# Measurements.net
KiCad netlist of a schematic drawn in Altium Designer
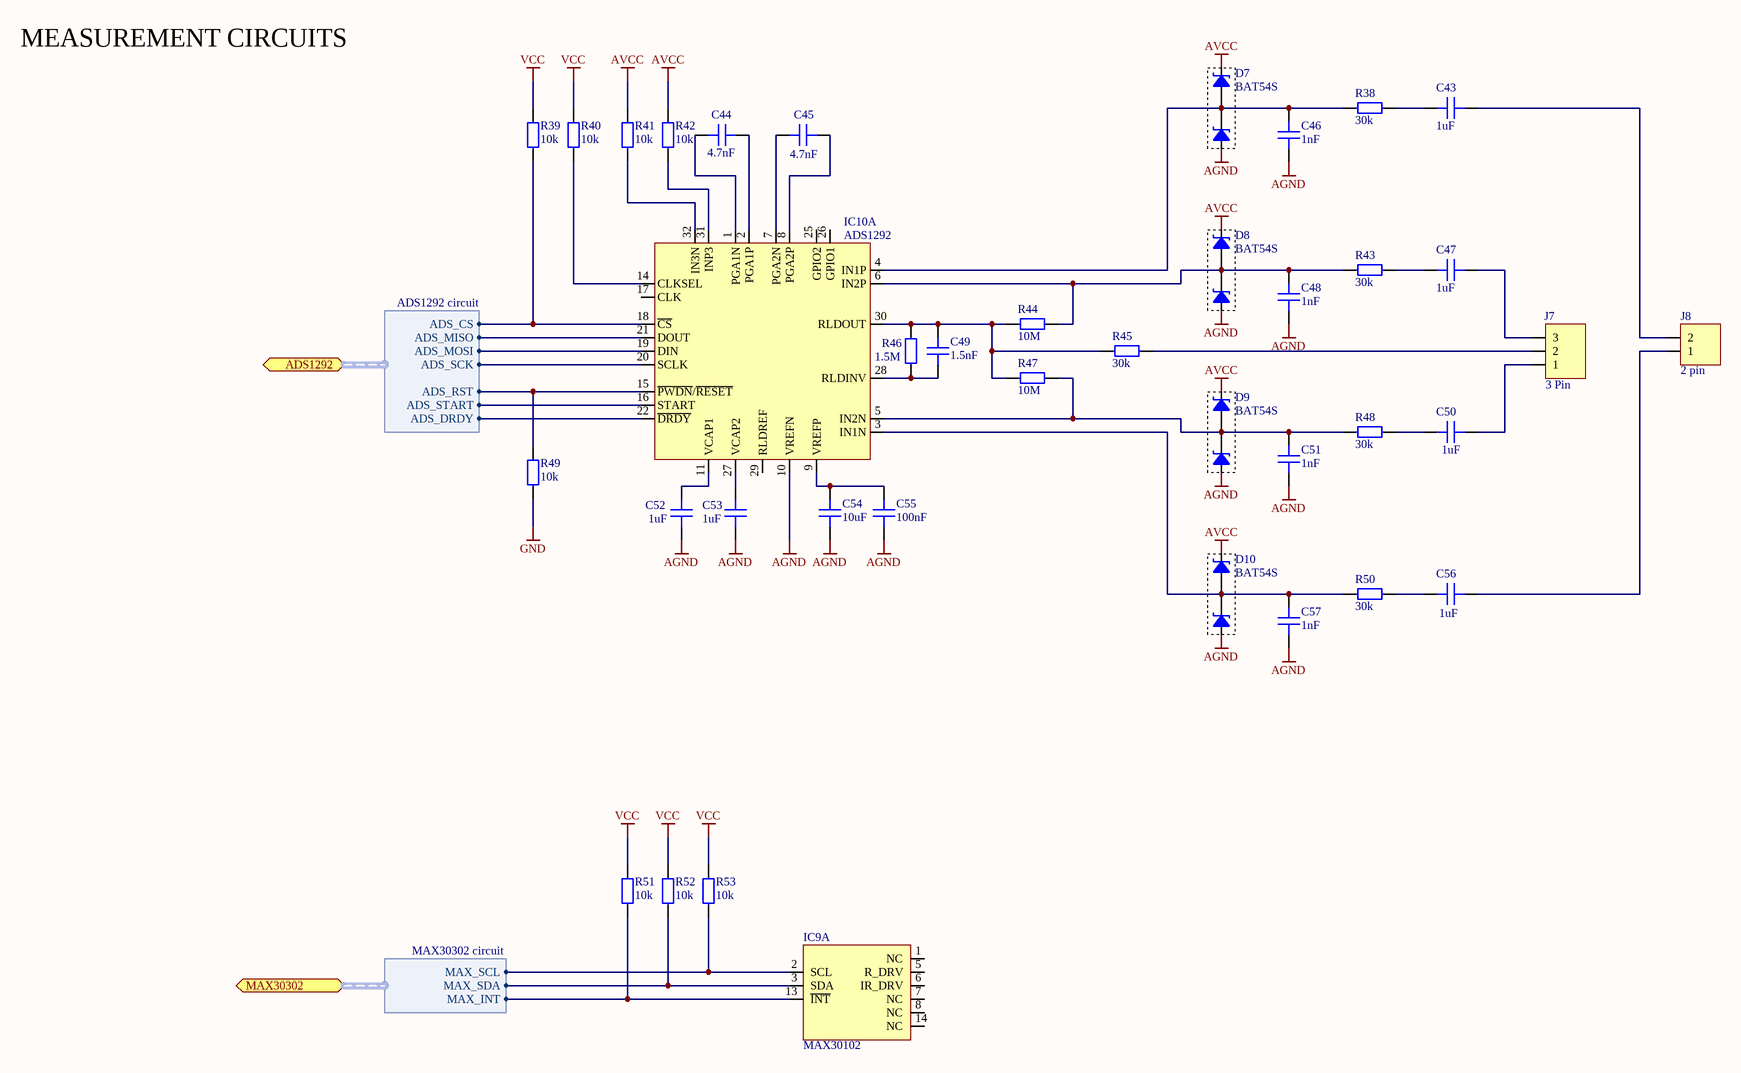
[diagram p0: Measurements.SchDoc]

(export (version "E")
  (design (tool "Eeschema 10.0.6"))
  (components
    (comp (ref "C43")
      (value "1uF")
      (footprint "CAP 0603")
      (description "SMT Capacitor")
      (libsource (lib "Passive") (part "Capacitor"))
    )
    (comp (ref "C44")
      (value "4.7nF")
      (footprint "CAP 0603")
      (description "SMT Capacitor")
      (libsource (lib "Passive") (part "Capacitor"))
    )
    (comp (ref "C45")
      (value "4.7nF")
      (footprint "CAP 0603")
      (description "SMT Capacitor")
      (libsource (lib "Passive") (part "Capacitor"))
    )
    (comp (ref "C46")
      (value "1nF")
      (footprint "CAP 0603")
      (description "SMT Capacitor")
      (libsource (lib "Passive") (part "Capacitor"))
    )
    (comp (ref "C47")
      (value "1uF")
      (footprint "CAP 0603")
      (description "SMT Capacitor")
      (libsource (lib "Passive") (part "Capacitor"))
    )
    (comp (ref "C48")
      (value "1nF")
      (footprint "CAP 0603")
      (description "SMT Capacitor")
      (libsource (lib "Passive") (part "Capacitor"))
    )
    (comp (ref "C49")
      (value "1.5nF")
      (footprint "CAP 0603")
      (description "SMT Capacitor")
      (libsource (lib "Passive") (part "Capacitor"))
    )
    (comp (ref "C50")
      (value "1uF")
      (footprint "CAP 0603")
      (description "SMT Capacitor")
      (libsource (lib "Passive") (part "Capacitor"))
    )
    (comp (ref "C51")
      (value "1nF")
      (footprint "CAP 0603")
      (description "SMT Capacitor")
      (libsource (lib "Passive") (part "Capacitor"))
    )
    (comp (ref "C52")
      (value "1uF")
      (footprint "CAP 0603")
      (description "SMT Capacitor")
      (libsource (lib "Passive") (part "Capacitor"))
    )
    (comp (ref "C53")
      (value "1uF")
      (footprint "CAP 0603")
      (description "SMT Capacitor")
      (libsource (lib "Passive") (part "Capacitor"))
    )
    (comp (ref "C54")
      (value "10uF")
      (footprint "CAP 0603")
      (description "SMT Capacitor")
      (libsource (lib "Passive") (part "Capacitor"))
    )
    (comp (ref "C55")
      (value "100nF")
      (footprint "CAP 0603")
      (description "SMT Capacitor")
      (libsource (lib "Passive") (part "Capacitor"))
    )
    (comp (ref "C56")
      (value "1uF")
      (footprint "CAP 0603")
      (description "SMT Capacitor")
      (libsource (lib "Passive") (part "Capacitor"))
    )
    (comp (ref "C57")
      (value "1nF")
      (footprint "CAP 0603")
      (description "SMT Capacitor")
      (libsource (lib "Passive") (part "Capacitor"))
    )
    (comp (ref "D7")
      (value "BAT54S")
      (footprint "SOT23")
      (description "Schottky barrier diodes")
      (libsource (lib "Diodes") (part "BAT54S"))
    )
    (comp (ref "D8")
      (value "BAT54S")
      (footprint "SOT23")
      (description "Schottky barrier diodes")
      (libsource (lib "Diodes") (part "BAT54S"))
    )
    (comp (ref "D9")
      (value "BAT54S")
      (footprint "SOT23")
      (description "Schottky barrier diodes")
      (libsource (lib "Diodes") (part "BAT54S"))
    )
    (comp (ref "D10")
      (value "BAT54S")
      (footprint "SOT23")
      (description "Schottky barrier diodes")
      (libsource (lib "Diodes") (part "BAT54S"))
    )
    (comp (ref "IC9")
      (value "MAX30102")
      (footprint "MAX30102")
      (description "Pulse Oximeter and Heart-Rate Sensor")
      (libsource (lib "IC") (part "MAX30102"))
    )
    (comp (ref "IC10")
      (value "ADS1292")
      (footprint "QFN 40 no via in pad")
      (description "ADS1292IRSMT Analog Front End - AFE Cmplt Lw Pwr Intgrtd AFE for ECG apps")
      (libsource (lib "IC") (part "ADS1292IRSMT"))
    )
    (comp (ref "J7")
      (value "3 Pin")
      (footprint "HDR 1x3 2.54")
      (description "3 pin header, male")
      (libsource (lib "Connectors") (part "3 Pin"))
    )
    (comp (ref "J8")
      (value "2 pin")
      (footprint "HDR 1x2 2.54")
      (description "2 pin header, male")
      (libsource (lib "Connectors") (part "2 pin"))
    )
    (comp (ref "R38")
      (value "30k")
      (footprint "RES 0603")
      (description "SMDResistor")
      (libsource (lib "Passive") (part "Resistor"))
    )
    (comp (ref "R39")
      (value "10k")
      (footprint "RES 0603")
      (description "SMDResistor")
      (libsource (lib "Passive") (part "Resistor"))
    )
    (comp (ref "R40")
      (value "10k")
      (footprint "RES 0603")
      (description "SMDResistor")
      (libsource (lib "Passive") (part "Resistor"))
    )
    (comp (ref "R41")
      (value "10k")
      (footprint "RES 0603")
      (description "SMDResistor")
      (libsource (lib "Passive") (part "Resistor"))
    )
    (comp (ref "R42")
      (value "10k")
      (footprint "RES 0603")
      (description "SMDResistor")
      (libsource (lib "Passive") (part "Resistor"))
    )
    (comp (ref "R43")
      (value "30k")
      (footprint "RES 0603")
      (description "SMDResistor")
      (libsource (lib "Passive") (part "Resistor"))
    )
    (comp (ref "R44")
      (value "10M")
      (footprint "RES 0603")
      (description "SMDResistor")
      (libsource (lib "Passive") (part "Resistor"))
    )
    (comp (ref "R45")
      (value "30k")
      (footprint "RES 0603")
      (description "SMDResistor")
      (libsource (lib "Passive") (part "Resistor"))
    )
    (comp (ref "R46")
      (value "1.5M")
      (footprint "RES 0603")
      (description "SMDResistor")
      (libsource (lib "Passive") (part "Resistor"))
    )
    (comp (ref "R47")
      (value "10M")
      (footprint "RES 0603")
      (description "SMDResistor")
      (libsource (lib "Passive") (part "Resistor"))
    )
    (comp (ref "R48")
      (value "30k")
      (footprint "RES 0603")
      (description "SMDResistor")
      (libsource (lib "Passive") (part "Resistor"))
    )
    (comp (ref "R49")
      (value "10k")
      (footprint "RES 0603")
      (description "SMDResistor")
      (libsource (lib "Passive") (part "Resistor"))
    )
    (comp (ref "R50")
      (value "30k")
      (footprint "RES 0603")
      (description "SMDResistor")
      (libsource (lib "Passive") (part "Resistor"))
    )
    (comp (ref "R51")
      (value "10k")
      (footprint "RES 0603")
      (description "SMDResistor")
      (libsource (lib "Passive") (part "Resistor"))
    )
    (comp (ref "R52")
      (value "10k")
      (footprint "RES 0603")
      (description "SMDResistor")
      (libsource (lib "Passive") (part "Resistor"))
    )
    (comp (ref "R53")
      (value "10k")
      (footprint "RES 0603")
      (description "SMDResistor")
      (libsource (lib "Passive") (part "Resistor"))
    )
  )
  (nets
    (net (code "4") (name "/ADS_CS") (class "Default")
      (node (ref "IC10") (pin "18") (pinfunction "~{CS}_18") (pintype "passive"))
      (node (ref "R39") (pin "1") (pinfunction "1_1") (pintype "passive"))
    )
    (net (code "5") (name "/ADS_DRDY") (class "Default")
      (node (ref "IC10") (pin "22") (pinfunction "~{DRDY}_22") (pintype "passive"))
    )
    (net (code "6") (name "/ADS_MISO") (class "Default")
      (node (ref "IC10") (pin "21") (pinfunction "DOUT_21") (pintype "passive"))
    )
    (net (code "7") (name "/ADS_MOSI") (class "Default")
      (node (ref "IC10") (pin "19") (pinfunction "DIN_19") (pintype "passive"))
    )
    (net (code "8") (name "/ADS_RST") (class "Default")
      (node (ref "IC10") (pin "15") (pinfunction "~{PWDN}/~{RESET}_15") (pintype "passive"))
      (node (ref "R49") (pin "2") (pinfunction "2_2") (pintype "passive"))
    )
    (net (code "9") (name "/ADS_SCK") (class "Default")
      (node (ref "IC10") (pin "20") (pinfunction "SCLK_20") (pintype "passive"))
    )
    (net (code "10") (name "/ADS_START") (class "Default")
      (node (ref "IC10") (pin "16") (pinfunction "START_16") (pintype "passive"))
    )
    (net (code "11") (name "/MAX_INT") (class "Default")
      (node (ref "IC9") (pin "13") (pinfunction "~{INT}_13") (pintype "passive"))
      (node (ref "R51") (pin "1") (pinfunction "1_1") (pintype "passive"))
    )
    (net (code "12") (name "/MAX_SCL") (class "Default")
      (node (ref "IC9") (pin "2") (pinfunction "SCL_2") (pintype "passive"))
      (node (ref "R53") (pin "1") (pinfunction "1_1") (pintype "passive"))
    )
    (net (code "13") (name "/MAX_SDA") (class "Default")
      (node (ref "IC9") (pin "3") (pinfunction "SDA_3") (pintype "passive"))
      (node (ref "R52") (pin "1") (pinfunction "1_1") (pintype "passive"))
    )
    (net (code "16") (name "AGND") (class "Default")
      (node (ref "C46") (pin "1") (pinfunction "1_1") (pintype "passive"))
      (node (ref "C48") (pin "1") (pinfunction "1_1") (pintype "passive"))
      (node (ref "C51") (pin "1") (pinfunction "1_1") (pintype "passive"))
      (node (ref "C52") (pin "1") (pinfunction "1_1") (pintype "passive"))
      (node (ref "C53") (pin "1") (pinfunction "1_1") (pintype "passive"))
      (node (ref "C54") (pin "1") (pinfunction "1_1") (pintype "passive"))
      (node (ref "C55") (pin "1") (pinfunction "1_1") (pintype "passive"))
      (node (ref "C57") (pin "1") (pinfunction "1_1") (pintype "passive"))
      (node (ref "D10") (pin "1") (pinfunction "1_1") (pintype "passive"))
      (node (ref "D7") (pin "1") (pinfunction "1_1") (pintype "passive"))
      (node (ref "D8") (pin "1") (pinfunction "1_1") (pintype "passive"))
      (node (ref "D9") (pin "1") (pinfunction "1_1") (pintype "passive"))
      (node (ref "IC10") (pin "10") (pinfunction "VREFN_10") (pintype "passive"))
    )
    (net (code "17") (name "AVCC") (class "Default")
      (node (ref "D10") (pin "2") (pinfunction "2_2") (pintype "passive"))
      (node (ref "D7") (pin "2") (pinfunction "2_2") (pintype "passive"))
      (node (ref "D8") (pin "2") (pinfunction "2_2") (pintype "passive"))
      (node (ref "D9") (pin "2") (pinfunction "2_2") (pintype "passive"))
      (node (ref "R41") (pin "2") (pinfunction "2_2") (pintype "passive"))
      (node (ref "R42") (pin "2") (pinfunction "2_2") (pintype "passive"))
    )
    (net (code "18") (name "GND") (class "Default")
      (node (ref "R49") (pin "1") (pinfunction "1_1") (pintype "passive"))
    )
    (net (code "19") (name "Net-(C43-Pad1)") (class "Default")
      (node (ref "C43") (pin "1") (pinfunction "1_1") (pintype "passive"))
      (node (ref "J8") (pin "2") (pinfunction "2_2") (pintype "passive"))
    )
    (net (code "20") (name "Net-(C43-Pad2)") (class "Default")
      (node (ref "C43") (pin "2") (pinfunction "2_2") (pintype "passive"))
      (node (ref "R38") (pin "1") (pinfunction "1_1") (pintype "passive"))
    )
    (net (code "21") (name "Net-(C47-Pad1)") (class "Default")
      (node (ref "C47") (pin "1") (pinfunction "1_1") (pintype "passive"))
      (node (ref "J7") (pin "3") (pinfunction "3_3") (pintype "passive"))
    )
    (net (code "22") (name "Net-(C47-Pad2)") (class "Default")
      (node (ref "C47") (pin "2") (pinfunction "2_2") (pintype "passive"))
      (node (ref "R43") (pin "1") (pinfunction "1_1") (pintype "passive"))
    )
    (net (code "23") (name "Net-(C50-Pad1)") (class "Default")
      (node (ref "C50") (pin "1") (pinfunction "1_1") (pintype "passive"))
      (node (ref "J7") (pin "1") (pinfunction "1_1") (pintype "passive"))
    )
    (net (code "24") (name "Net-(C50-Pad2)") (class "Default")
      (node (ref "C50") (pin "2") (pinfunction "2_2") (pintype "passive"))
      (node (ref "R48") (pin "1") (pinfunction "1_1") (pintype "passive"))
    )
    (net (code "25") (name "Net-(C56-Pad1)") (class "Default")
      (node (ref "C56") (pin "1") (pinfunction "1_1") (pintype "passive"))
      (node (ref "J8") (pin "1") (pinfunction "1_1") (pintype "passive"))
    )
    (net (code "26") (name "Net-(C56-Pad2)") (class "Default")
      (node (ref "C56") (pin "2") (pinfunction "2_2") (pintype "passive"))
      (node (ref "R50") (pin "1") (pinfunction "1_1") (pintype "passive"))
    )
    (net (code "27") (name "Net-(IC10A-CLKSEL)") (class "Default")
      (node (ref "IC10") (pin "14") (pinfunction "CLKSEL_14") (pintype "passive"))
      (node (ref "R40") (pin "1") (pinfunction "1_1") (pintype "passive"))
    )
    (net (code "28") (name "Net-(IC10A-IN1N)") (class "Default")
      (node (ref "C57") (pin "2") (pinfunction "2_2") (pintype "passive"))
      (node (ref "D10") (pin "3") (pinfunction "3_3") (pintype "passive"))
      (node (ref "IC10") (pin "3") (pinfunction "IN1N_3") (pintype "passive"))
      (node (ref "R50") (pin "2") (pinfunction "2_2") (pintype "passive"))
    )
    (net (code "29") (name "Net-(IC10A-IN1P)") (class "Default")
      (node (ref "C46") (pin "2") (pinfunction "2_2") (pintype "passive"))
      (node (ref "D7") (pin "3") (pinfunction "3_3") (pintype "passive"))
      (node (ref "IC10") (pin "4") (pinfunction "IN1P_4") (pintype "passive"))
      (node (ref "R38") (pin "2") (pinfunction "2_2") (pintype "passive"))
    )
    (net (code "30") (name "Net-(IC10A-IN2N)") (class "Default")
      (node (ref "C51") (pin "2") (pinfunction "2_2") (pintype "passive"))
      (node (ref "D9") (pin "3") (pinfunction "3_3") (pintype "passive"))
      (node (ref "IC10") (pin "5") (pinfunction "IN2N_5") (pintype "passive"))
      (node (ref "R47") (pin "1") (pinfunction "1_1") (pintype "passive"))
      (node (ref "R48") (pin "2") (pinfunction "2_2") (pintype "passive"))
    )
    (net (code "31") (name "Net-(IC10A-IN2P)") (class "Default")
      (node (ref "C48") (pin "2") (pinfunction "2_2") (pintype "passive"))
      (node (ref "D8") (pin "3") (pinfunction "3_3") (pintype "passive"))
      (node (ref "IC10") (pin "6") (pinfunction "IN2P_6") (pintype "passive"))
      (node (ref "R43") (pin "2") (pinfunction "2_2") (pintype "passive"))
      (node (ref "R44") (pin "1") (pinfunction "1_1") (pintype "passive"))
    )
    (net (code "32") (name "Net-(IC10A-IN3N)") (class "Default")
      (node (ref "IC10") (pin "32") (pinfunction "IN3N_32") (pintype "passive"))
      (node (ref "R41") (pin "1") (pinfunction "1_1") (pintype "passive"))
    )
    (net (code "33") (name "Net-(IC10A-INP3)") (class "Default")
      (node (ref "IC10") (pin "31") (pinfunction "INP3_31") (pintype "passive"))
      (node (ref "R42") (pin "1") (pinfunction "1_1") (pintype "passive"))
    )
    (net (code "34") (name "Net-(IC10A-PGA1N)") (class "Default")
      (node (ref "C44") (pin "1") (pinfunction "1_1") (pintype "passive"))
      (node (ref "IC10") (pin "1") (pinfunction "PGA1N_1") (pintype "passive"))
    )
    (net (code "35") (name "Net-(IC10A-PGA1P)") (class "Default")
      (node (ref "C44") (pin "2") (pinfunction "2_2") (pintype "passive"))
      (node (ref "IC10") (pin "2") (pinfunction "PGA1P_2") (pintype "passive"))
    )
    (net (code "36") (name "Net-(IC10A-PGA2N)") (class "Default")
      (node (ref "C45") (pin "1") (pinfunction "1_1") (pintype "passive"))
      (node (ref "IC10") (pin "7") (pinfunction "PGA2N_7") (pintype "passive"))
    )
    (net (code "37") (name "Net-(IC10A-PGA2P)") (class "Default")
      (node (ref "C45") (pin "2") (pinfunction "2_2") (pintype "passive"))
      (node (ref "IC10") (pin "8") (pinfunction "PGA2P_8") (pintype "passive"))
    )
    (net (code "38") (name "Net-(IC10A-RLDINV)") (class "Default")
      (node (ref "C49") (pin "1") (pinfunction "1_1") (pintype "passive"))
      (node (ref "IC10") (pin "28") (pinfunction "RLDINV_28") (pintype "passive"))
      (node (ref "R46") (pin "1") (pinfunction "1_1") (pintype "passive"))
    )
    (net (code "39") (name "Net-(IC10A-RLDOUT)") (class "Default")
      (node (ref "C49") (pin "2") (pinfunction "2_2") (pintype "passive"))
      (node (ref "IC10") (pin "30") (pinfunction "RLDOUT_30") (pintype "passive"))
      (node (ref "R44") (pin "2") (pinfunction "2_2") (pintype "passive"))
      (node (ref "R45") (pin "2") (pinfunction "2_2") (pintype "passive"))
      (node (ref "R46") (pin "2") (pinfunction "2_2") (pintype "passive"))
      (node (ref "R47") (pin "2") (pinfunction "2_2") (pintype "passive"))
    )
    (net (code "40") (name "Net-(IC10A-VCAP1)") (class "Default")
      (node (ref "C52") (pin "2") (pinfunction "2_2") (pintype "passive"))
      (node (ref "IC10") (pin "11") (pinfunction "VCAP1_11") (pintype "passive"))
    )
    (net (code "41") (name "Net-(IC10A-VCAP2)") (class "Default")
      (node (ref "C53") (pin "2") (pinfunction "2_2") (pintype "passive"))
      (node (ref "IC10") (pin "27") (pinfunction "VCAP2_27") (pintype "passive"))
    )
    (net (code "42") (name "Net-(IC10A-VREFP)") (class "Default")
      (node (ref "C54") (pin "2") (pinfunction "2_2") (pintype "passive"))
      (node (ref "C55") (pin "2") (pinfunction "2_2") (pintype "passive"))
      (node (ref "IC10") (pin "9") (pinfunction "VREFP_9") (pintype "passive"))
    )
    (net (code "43") (name "Net-(J7-Pad2)") (class "Default")
      (node (ref "J7") (pin "2") (pinfunction "2_2") (pintype "passive"))
      (node (ref "R45") (pin "1") (pinfunction "1_1") (pintype "passive"))
    )
    (net (code "44") (name "VCC") (class "Default")
      (node (ref "R39") (pin "2") (pinfunction "2_2") (pintype "passive"))
      (node (ref "R40") (pin "2") (pinfunction "2_2") (pintype "passive"))
      (node (ref "R51") (pin "2") (pinfunction "2_2") (pintype "passive"))
      (node (ref "R52") (pin "2") (pinfunction "2_2") (pintype "passive"))
      (node (ref "R53") (pin "2") (pinfunction "2_2") (pintype "passive"))
    )
    (net (code "45") (name "unconnected-(IC9A-IR_DRV-Pad6)") (class "Default")
      (node (ref "IC9") (pin "6") (pinfunction "IR_DRV_6") (pintype "passive"))
    )
    (net (code "46") (name "unconnected-(IC9A-NC-Pad1)") (class "Default")
      (node (ref "IC9") (pin "1") (pinfunction "NC_1") (pintype "passive"))
    )
    (net (code "47") (name "unconnected-(IC9A-NC-Pad7)") (class "Default")
      (node (ref "IC9") (pin "7") (pinfunction "NC_7") (pintype "passive"))
    )
    (net (code "48") (name "unconnected-(IC9A-NC-Pad8)") (class "Default")
      (node (ref "IC9") (pin "8") (pinfunction "NC_8") (pintype "passive"))
    )
    (net (code "49") (name "unconnected-(IC9A-NC-Pad14)") (class "Default")
      (node (ref "IC9") (pin "14") (pinfunction "NC_14") (pintype "passive"))
    )
    (net (code "50") (name "unconnected-(IC9A-R_DRV-Pad5)") (class "Default")
      (node (ref "IC9") (pin "5") (pinfunction "R_DRV_5") (pintype "passive"))
    )
    (net (code "51") (name "unconnected-(IC10A-CLK-Pad17)") (class "Default")
      (node (ref "IC10") (pin "17") (pinfunction "CLK_17") (pintype "passive"))
    )
    (net (code "52") (name "unconnected-(IC10A-GPIO1-Pad26)") (class "Default")
      (node (ref "IC10") (pin "26") (pinfunction "GPIO1_26") (pintype "passive"))
    )
    (net (code "53") (name "unconnected-(IC10A-GPIO2-Pad25)") (class "Default")
      (node (ref "IC10") (pin "25") (pinfunction "GPIO2_25") (pintype "passive"))
    )
    (net (code "54") (name "unconnected-(IC10A-RLDREF-Pad29)") (class "Default")
      (node (ref "IC10") (pin "29") (pinfunction "RLDREF_29") (pintype "passive"))
    )
  )
)
